# ADC.net
KiCad netlist of a schematic drawn in Altium Designer
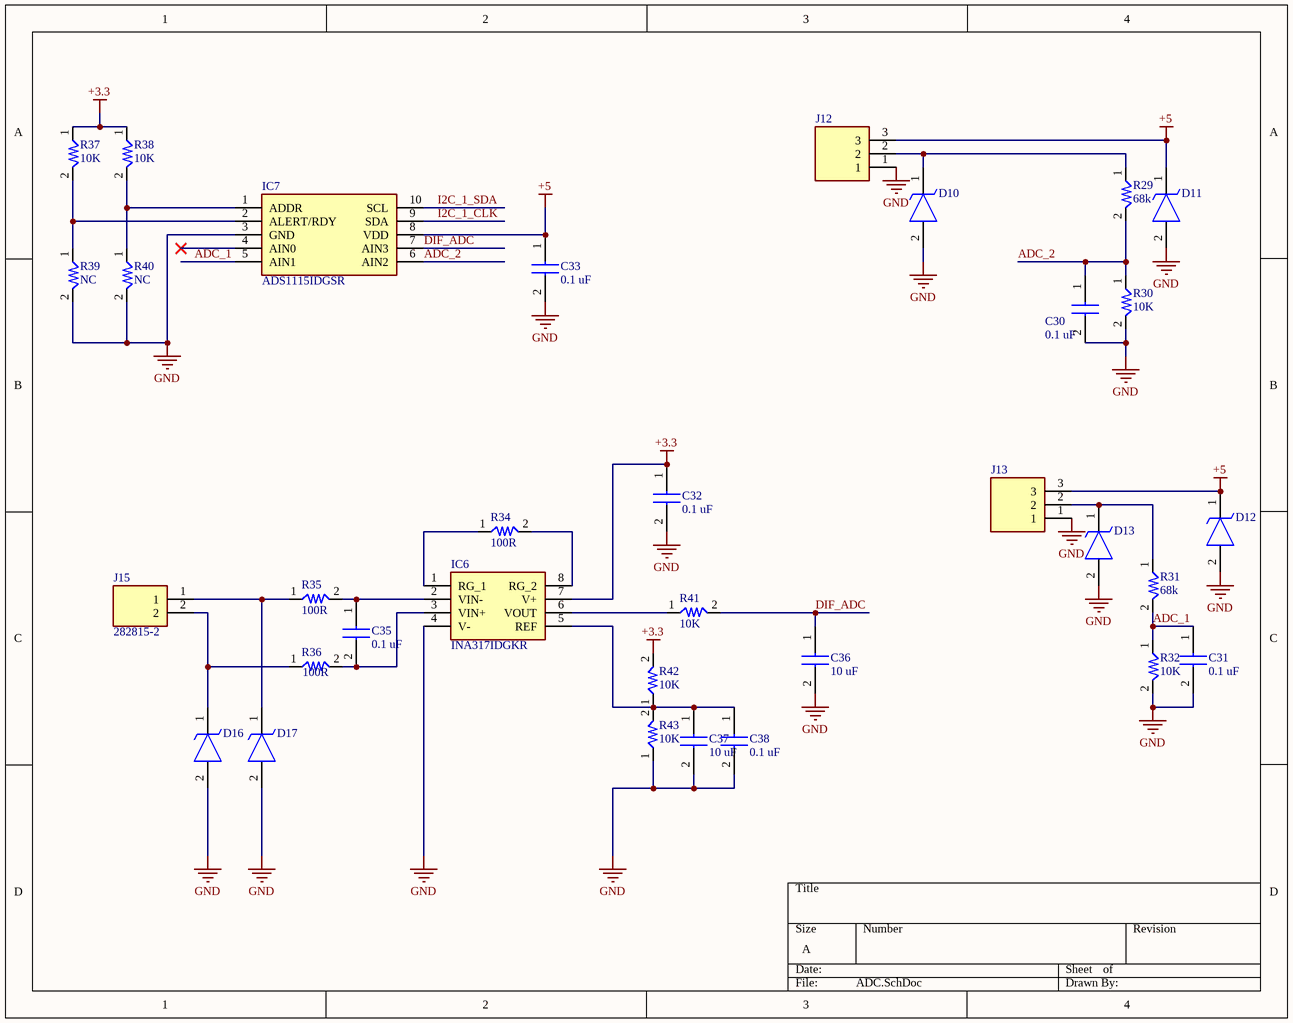
[diagram p0: ADC.SchDoc]

(export (version "E")
  (design (tool "Eeschema 10.0.6"))
  (components
    (comp (ref "C30")
      (value "0.1 uF")
      (footprint "CAP0603")
      (description "Capacitor")
      (fields
        (field (name "MANUFACTURER_PART_NUMBER") "CC0603KRX7R9BB104")
        (field (name "MOUSER PART NUMBER") "603-CC603KRX7R9BB104")
      )
      (libsource (lib "Valve_Controller_Lib") (part "CC0603KRX7R9BB104"))
    )
    (comp (ref "C31")
      (value "0.1 uF")
      (footprint "CAP0603")
      (description "Capacitor")
      (fields
        (field (name "MANUFACTURER_PART_NUMBER") "CC0603KRX7R9BB104")
        (field (name "MOUSER PART NUMBER") "603-CC603KRX7R9BB104")
      )
      (libsource (lib "Valve_Controller_Lib") (part "CC0603KRX7R9BB104"))
    )
    (comp (ref "C32")
      (value "0.1 uF")
      (footprint "CAP0603")
      (description "Capacitor")
      (fields
        (field (name "MANUFACTURER_PART_NUMBER") "CC0603KRX7R9BB104")
        (field (name "MOUSER PART NUMBER") "603-CC603KRX7R9BB104")
      )
      (libsource (lib "Valve_Controller_Lib") (part "CC0603KRX7R9BB104"))
    )
    (comp (ref "C33")
      (value "0.1 uF")
      (footprint "CAP0603")
      (description "Capacitor")
      (fields
        (field (name "MANUFACTURER_PART_NUMBER") "CC0603KRX7R9BB104")
        (field (name "MOUSER PART NUMBER") "603-CC603KRX7R9BB104")
      )
      (libsource (lib "Valve_Controller_Lib") (part "CC0603KRX7R9BB104"))
    )
    (comp (ref "C35")
      (value "0.1 uF")
      (footprint "CAP0603")
      (description "Capacitor")
      (fields
        (field (name "MANUFACTURER_PART_NUMBER") "CC0603KRX7R9BB104")
        (field (name "MOUSER PART NUMBER") "603-CC603KRX7R9BB104")
      )
      (libsource (lib "Valve_Controller_Lib") (part "CC0603KRX7R9BB104"))
    )
    (comp (ref "C36")
      (value "10 uF")
      (footprint "CAP0603")
      (description "Capacitor")
      (fields
        (field (name "MANUFACTURER_PART_NUMBER") "CC0603KRX7R9BB104")
        (field (name "MOUSER PART NUMBER") "603-CC603KRX7R9BB104")
      )
      (libsource (lib "Valve_Controller_Lib") (part "CC0603KRX7R9BB104"))
    )
    (comp (ref "C37")
      (value "10 uF")
      (footprint "CAP0603")
      (description "Capacitor")
      (fields
        (field (name "MANUFACTURER_PART_NUMBER") "CC0603KRX7R9BB104")
        (field (name "MOUSER PART NUMBER") "603-CC603KRX7R9BB104")
      )
      (libsource (lib "Valve_Controller_Lib") (part "CC0603KRX7R9BB104"))
    )
    (comp (ref "C38")
      (value "0.1 uF")
      (footprint "CAP0603")
      (description "Capacitor")
      (fields
        (field (name "MANUFACTURER_PART_NUMBER") "CC0603KRX7R9BB104")
        (field (name "MOUSER PART NUMBER") "603-CC603KRX7R9BB104")
      )
      (libsource (lib "Valve_Controller_Lib") (part "CC0603KRX7R9BB104"))
    )
    (comp (ref "D10")
      (value "SMBJ5.0A")
      (footprint "SamacSys:SMBJ12A")
      (description "TVS Diode (Uni-directional)")
      (libsource (lib "*") (part "SMBJ5.0A"))
    )
    (comp (ref "D11")
      (value "SMBJ5.0A")
      (footprint "SamacSys:SMBJ12A")
      (description "TVS Diode (Uni-directional)")
      (libsource (lib "*") (part "SMBJ5.0A"))
    )
    (comp (ref "D12")
      (value "SMBJ5.0A")
      (footprint "SamacSys:SMBJ12A")
      (description "TVS Diode (Uni-directional)")
      (libsource (lib "*") (part "SMBJ5.0A"))
    )
    (comp (ref "D13")
      (value "SMBJ5.0A")
      (footprint "SamacSys:SMBJ12A")
      (description "TVS Diode (Uni-directional)")
      (libsource (lib "*") (part "SMBJ5.0A"))
    )
    (comp (ref "D16")
      (value "SMBJ5.0A")
      (footprint "SamacSys:SMBJ12A")
      (description "TVS Diode (Uni-directional)")
      (libsource (lib "*") (part "SMBJ5.0A"))
    )
    (comp (ref "D17")
      (value "SMBJ5.0A")
      (footprint "SamacSys:SMBJ12A")
      (description "TVS Diode (Uni-directional)")
      (libsource (lib "*") (part "SMBJ5.0A"))
    )
    (comp (ref "IC6")
      (value "INA317IDGKR")
      (footprint "SamacSys:SOP65P490X110-8N")
      (description "Integrated Circuit")
      (fields (field (name "MOUSER PART NUMBER") "595-INA317IDGKR"))
      (libsource (lib "*") (part "INA317IDGKR"))
    )
    (comp (ref "IC7")
      (value "ADS1115IDGSR")
      (footprint "SamacSys:SOP50P490X110-10N")
      (description "Integrated Circuit")
      (fields (field (name "MOUSER PART NUMBER") "595-ADS1115IDGSR"))
      (libsource (lib "*") (part "ADS1115IDGSR"))
    )
    (comp (ref "J12")
      (value "282815-3")
      (footprint "SamacSys:2828153")
      (description "Connector")
      (fields (field (name "MOUSER PART NUMBER") "571-282815-3"))
      (libsource (lib "*") (part "282815-3"))
    )
    (comp (ref "J13")
      (value "282815-3")
      (footprint "SamacSys:2828153")
      (description "Connector")
      (fields (field (name "MOUSER PART NUMBER") "571-282815-3"))
      (libsource (lib "*") (part "282815-3"))
    )
    (comp (ref "J15")
      (value "282815-2")
      (footprint "SamacSys:SHDRRA2W102P0X508_1X2_1016X1200X850P")
      (description "Connector")
      (fields (field (name "MOUSER PART NUMBER") "571-282815-2"))
      (libsource (lib "*") (part "282815-2"))
    )
    (comp (ref "R29")
      (value "68k")
      (footprint "RES0603")
      (description "Resistor")
      (fields (field (name "MANUFACTURER_PART_NUMBER") "0603WAF1001T5E"))
      (libsource (lib "Valve_Controller_Lib") (part "RES"))
    )
    (comp (ref "R30")
      (value "10K")
      (footprint "RES0603")
      (description "Resistor")
      (fields (field (name "MANUFACTURER_PART_NUMBER") "0603WAF1001T5E"))
      (libsource (lib "Valve_Controller_Lib") (part "RES"))
    )
    (comp (ref "R31")
      (value "68k")
      (footprint "RES0603")
      (description "Resistor")
      (fields (field (name "MANUFACTURER_PART_NUMBER") "0603WAF1001T5E"))
      (libsource (lib "Valve_Controller_Lib") (part "RES"))
    )
    (comp (ref "R32")
      (value "10K")
      (footprint "RES0603")
      (description "Resistor")
      (fields (field (name "MANUFACTURER_PART_NUMBER") "0603WAF1001T5E"))
      (libsource (lib "Valve_Controller_Lib") (part "RES"))
    )
    (comp (ref "R34")
      (value "100R")
      (footprint "RES0603")
      (description "Resistor")
      (fields (field (name "MANUFACTURER_PART_NUMBER") "0603WAF1001T5E"))
      (libsource (lib "Valve_Controller_Lib") (part "RES"))
    )
    (comp (ref "R35")
      (value "100R")
      (footprint "RES0603")
      (description "Resistor")
      (fields (field (name "MANUFACTURER_PART_NUMBER") "0603WAF1001T5E"))
      (libsource (lib "Valve_Controller_Lib") (part "RES"))
    )
    (comp (ref "R36")
      (value "100R")
      (footprint "RES0603")
      (description "Resistor")
      (fields (field (name "MANUFACTURER_PART_NUMBER") "0603WAF1001T5E"))
      (libsource (lib "Valve_Controller_Lib") (part "RES"))
    )
    (comp (ref "R37")
      (value "10K")
      (footprint "RES0603")
      (description "Resistor")
      (fields (field (name "MANUFACTURER_PART_NUMBER") "0603WAF1001T5E"))
      (libsource (lib "Valve_Controller_Lib") (part "RES"))
    )
    (comp (ref "R38")
      (value "10K")
      (footprint "RES0603")
      (description "Resistor")
      (fields (field (name "MANUFACTURER_PART_NUMBER") "0603WAF1001T5E"))
      (libsource (lib "Valve_Controller_Lib") (part "RES"))
    )
    (comp (ref "R39")
      (value "NC")
      (footprint "RES0603")
      (description "Resistor")
      (fields (field (name "MANUFACTURER_PART_NUMBER") "0603WAF1001T5E"))
      (libsource (lib "Valve_Controller_Lib") (part "RES"))
    )
    (comp (ref "R40")
      (value "NC")
      (footprint "RES0603")
      (description "Resistor")
      (fields (field (name "MANUFACTURER_PART_NUMBER") "0603WAF1001T5E"))
      (libsource (lib "Valve_Controller_Lib") (part "RES"))
    )
    (comp (ref "R41")
      (value "10K")
      (footprint "RES0603")
      (description "Resistor")
      (fields (field (name "MANUFACTURER_PART_NUMBER") "0603WAF1001T5E"))
      (libsource (lib "Valve_Controller_Lib") (part "RES"))
    )
    (comp (ref "R42")
      (value "10K")
      (footprint "RES0603")
      (description "Resistor")
      (fields (field (name "MANUFACTURER_PART_NUMBER") "0603WAF1001T5E"))
      (libsource (lib "Valve_Controller_Lib") (part "RES"))
    )
    (comp (ref "R43")
      (value "10K")
      (footprint "RES0603")
      (description "Resistor")
      (fields (field (name "MANUFACTURER_PART_NUMBER") "0603WAF1001T5E"))
      (libsource (lib "Valve_Controller_Lib") (part "RES"))
    )
  )
  (nets
    (net (code "1") (name "+3.3") (class "Default")
      (node (ref "C32") (pin "1") (pinfunction "1_1") (pintype "passive"))
      (node (ref "IC6") (pin "7") (pinfunction "V+_7") (pintype "passive"))
      (node (ref "R37") (pin "1") (pinfunction "1_1") (pintype "passive"))
      (node (ref "R38") (pin "1") (pinfunction "1_1") (pintype "passive"))
      (node (ref "R42") (pin "2") (pinfunction "2_2") (pintype "passive"))
    )
    (net (code "2") (name "+5") (class "Default")
      (node (ref "C33") (pin "1") (pinfunction "1_1") (pintype "passive"))
      (node (ref "D11") (pin "1") (pinfunction "K_1") (pintype "passive"))
      (node (ref "D12") (pin "1") (pinfunction "K_1") (pintype "passive"))
      (node (ref "IC7") (pin "8") (pinfunction "VDD_8") (pintype "passive"))
      (node (ref "J12") (pin "3") (pinfunction "3_3") (pintype "passive"))
      (node (ref "J13") (pin "3") (pinfunction "3_3") (pintype "passive"))
    )
    (net (code "3") (name "/ADC_1") (class "Default")
      (node (ref "C31") (pin "1") (pinfunction "1_1") (pintype "passive"))
      (node (ref "IC7") (pin "5") (pinfunction "AIN1_5") (pintype "passive"))
      (node (ref "R31") (pin "2") (pinfunction "2_2") (pintype "passive"))
      (node (ref "R32") (pin "1") (pinfunction "1_1") (pintype "passive"))
    )
    (net (code "4") (name "/ADC_2") (class "Default")
      (node (ref "C30") (pin "1") (pinfunction "1_1") (pintype "passive"))
      (node (ref "IC7") (pin "6") (pinfunction "AIN2_6") (pintype "passive"))
      (node (ref "R29") (pin "2") (pinfunction "2_2") (pintype "passive"))
      (node (ref "R30") (pin "1") (pinfunction "1_1") (pintype "passive"))
    )
    (net (code "5") (name "/DIF_ADC") (class "Default")
      (node (ref "C36") (pin "1") (pinfunction "1_1") (pintype "passive"))
      (node (ref "IC7") (pin "7") (pinfunction "AIN3_7") (pintype "passive"))
      (node (ref "R41") (pin "2") (pinfunction "2_2") (pintype "passive"))
    )
    (net (code "6") (name "/I2C_1_CLK") (class "Default")
      (node (ref "IC7") (pin "9") (pinfunction "SDA_9") (pintype "passive"))
    )
    (net (code "7") (name "/I2C_1_SDA") (class "Default")
      (node (ref "IC7") (pin "10") (pinfunction "SCL_10") (pintype "passive"))
    )
    (net (code "8") (name "GND") (class "Default")
      (node (ref "C30") (pin "2") (pinfunction "2_2") (pintype "passive"))
      (node (ref "C31") (pin "2") (pinfunction "2_2") (pintype "passive"))
      (node (ref "C32") (pin "2") (pinfunction "2_2") (pintype "passive"))
      (node (ref "C33") (pin "2") (pinfunction "2_2") (pintype "passive"))
      (node (ref "C36") (pin "2") (pinfunction "2_2") (pintype "passive"))
      (node (ref "C37") (pin "2") (pinfunction "2_2") (pintype "passive"))
      (node (ref "C38") (pin "2") (pinfunction "2_2") (pintype "passive"))
      (node (ref "D10") (pin "2") (pinfunction "A_2") (pintype "passive"))
      (node (ref "D11") (pin "2") (pinfunction "A_2") (pintype "passive"))
      (node (ref "D12") (pin "2") (pinfunction "A_2") (pintype "passive"))
      (node (ref "D13") (pin "2") (pinfunction "A_2") (pintype "passive"))
      (node (ref "D16") (pin "2") (pinfunction "A_2") (pintype "passive"))
      (node (ref "D17") (pin "2") (pinfunction "A_2") (pintype "passive"))
      (node (ref "IC6") (pin "4") (pinfunction "V-_4") (pintype "passive"))
      (node (ref "IC7") (pin "3") (pinfunction "GND_3") (pintype "passive"))
      (node (ref "J12") (pin "1") (pinfunction "1_1") (pintype "passive"))
      (node (ref "J13") (pin "1") (pinfunction "1_1") (pintype "passive"))
      (node (ref "R30") (pin "2") (pinfunction "2_2") (pintype "passive"))
      (node (ref "R32") (pin "2") (pinfunction "2_2") (pintype "passive"))
      (node (ref "R39") (pin "2") (pinfunction "2_2") (pintype "passive"))
      (node (ref "R40") (pin "2") (pinfunction "2_2") (pintype "passive"))
      (node (ref "R43") (pin "1") (pinfunction "1_1") (pintype "passive"))
    )
    (net (code "9") (name "Net-(D10-K)") (class "Default")
      (node (ref "D10") (pin "1") (pinfunction "K_1") (pintype "passive"))
      (node (ref "J12") (pin "2") (pinfunction "2_2") (pintype "passive"))
      (node (ref "R29") (pin "1") (pinfunction "1_1") (pintype "passive"))
    )
    (net (code "10") (name "Net-(D13-K)") (class "Default")
      (node (ref "D13") (pin "1") (pinfunction "K_1") (pintype "passive"))
      (node (ref "J13") (pin "2") (pinfunction "2_2") (pintype "passive"))
      (node (ref "R31") (pin "1") (pinfunction "1_1") (pintype "passive"))
    )
    (net (code "11") (name "Net-(D16-K)") (class "Default")
      (node (ref "D16") (pin "1") (pinfunction "K_1") (pintype "passive"))
      (node (ref "J15") (pin "2") (pinfunction "2_2") (pintype "passive"))
      (node (ref "R36") (pin "1") (pinfunction "1_1") (pintype "passive"))
    )
    (net (code "12") (name "Net-(D17-K)") (class "Default")
      (node (ref "D17") (pin "1") (pinfunction "K_1") (pintype "passive"))
      (node (ref "J15") (pin "1") (pinfunction "1_1") (pintype "passive"))
      (node (ref "R35") (pin "1") (pinfunction "1_1") (pintype "passive"))
    )
    (net (code "13") (name "Net-(IC6-REF)") (class "Default")
      (node (ref "C37") (pin "1") (pinfunction "1_1") (pintype "passive"))
      (node (ref "C38") (pin "1") (pinfunction "1_1") (pintype "passive"))
      (node (ref "IC6") (pin "5") (pinfunction "REF_5") (pintype "passive"))
      (node (ref "R42") (pin "1") (pinfunction "1_1") (pintype "passive"))
      (node (ref "R43") (pin "2") (pinfunction "2_2") (pintype "passive"))
    )
    (net (code "14") (name "Net-(IC6-RG_1)") (class "Default")
      (node (ref "IC6") (pin "1") (pinfunction "RG_1_1") (pintype "passive"))
      (node (ref "R34") (pin "1") (pinfunction "1_1") (pintype "passive"))
    )
    (net (code "15") (name "Net-(IC6-RG_2)") (class "Default")
      (node (ref "IC6") (pin "8") (pinfunction "RG_2_8") (pintype "passive"))
      (node (ref "R34") (pin "2") (pinfunction "2_2") (pintype "passive"))
    )
    (net (code "16") (name "Net-(IC6-VIN+)") (class "Default")
      (node (ref "C35") (pin "2") (pinfunction "2_2") (pintype "passive"))
      (node (ref "IC6") (pin "3") (pinfunction "VIN+_3") (pintype "passive"))
      (node (ref "R36") (pin "2") (pinfunction "2_2") (pintype "passive"))
    )
    (net (code "17") (name "Net-(IC6-VIN-)") (class "Default")
      (node (ref "C35") (pin "1") (pinfunction "1_1") (pintype "passive"))
      (node (ref "IC6") (pin "2") (pinfunction "VIN-_2") (pintype "passive"))
      (node (ref "R35") (pin "2") (pinfunction "2_2") (pintype "passive"))
    )
    (net (code "18") (name "Net-(IC6-VOUT)") (class "Default")
      (node (ref "IC6") (pin "6") (pinfunction "VOUT_6") (pintype "passive"))
      (node (ref "R41") (pin "1") (pinfunction "1_1") (pintype "passive"))
    )
    (net (code "19") (name "Net-(IC7-ADDR)") (class "Default")
      (node (ref "IC7") (pin "1") (pinfunction "ADDR_1") (pintype "passive"))
      (node (ref "R38") (pin "2") (pinfunction "2_2") (pintype "passive"))
      (node (ref "R40") (pin "1") (pinfunction "1_1") (pintype "passive"))
    )
    (net (code "20") (name "Net-(IC7-ALERT{slash}RDY)") (class "Default")
      (node (ref "IC7") (pin "2") (pinfunction "ALERT/RDY_2") (pintype "passive"))
      (node (ref "R37") (pin "2") (pinfunction "2_2") (pintype "passive"))
      (node (ref "R39") (pin "1") (pinfunction "1_1") (pintype "passive"))
    )
    (net (code "21") (name "unconnected-(IC7-AIN0-Pad4)") (class "Default")
      (node (ref "IC7") (pin "4") (pinfunction "AIN0_4") (pintype "passive+no_connect"))
    )
  )
)
